# RELAY18.net
KiCad netlist of a schematic drawn in Altium Designer
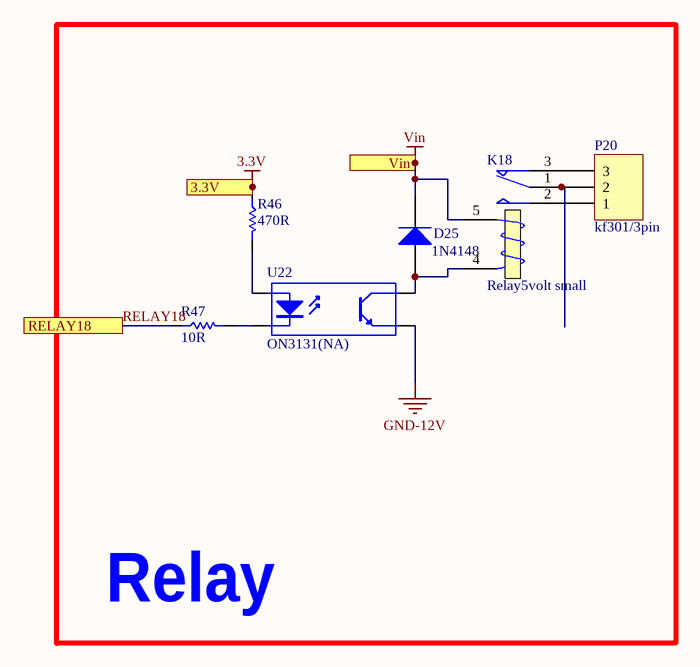
[diagram p0: RELAY18.SchDoc]

(export (version "E")
  (design (tool "Eeschema 10.0.6"))
  (components
    (comp (ref "D25")
      (value "1N4148")
      (footprint "sod123")
      (description "1 Amp General Purpose Rectifier")
      (fields (field (name "PUBLISHER") "Altium Limited"))
      (libsource (lib "Miscellaneous Devices") (part "Diode 1N4007"))
    )
    (comp (ref "K18")
      (value "Relay5volt small")
      (footprint "relay5_childern")
      (description "SPDT Relay")
      (fields (field (name "PUBLISHER") "Altium Limited"))
      (libsource (lib "FLIB") (part "Relay"))
    )
    (comp (ref "P20")
      (value "kf301/3pin")
      (footprint "Blue Connector 1*3 -kf301")
      (fields (field (name "PUBLISHER") "Altium Limited"))
      (libsource (lib "Miscellaneous Connectors") (part "Header 3"))
    )
    (comp (ref "R46")
      (value "470R")
      (footprint "0805/resistor")
      (description "Resistor")
      (fields (field (name "TOLERANCE") "5%") (field (name "POWER") "1/8 W"))
      (libsource (lib "skille") (part "Resistor"))
    )
    (comp (ref "R47")
      (value "10R")
      (footprint "0805/resistor")
      (description "Resistor")
      (fields (field (name "TOLERANCE") "5%") (field (name "POWER") "1/8 W"))
      (libsource (lib "skille") (part "Resistor"))
    )
    (comp (ref "U22")
      (value "ON3131(NA)")
      (footprint "OPTO_COUPLER")
      (description "4-Pin Phototransistor Optocoupler")
      (fields (field (name "PUBLISHER") "Altium Limited"))
      (libsource (lib "skille") (part "Optoisolator1"))
    )
  )
  (nets
    (net (code "1") (name "/RELAY18") (class "Default")
      (node (ref "R47") (pin "1") (pinfunction "1_1") (pintype "passive"))
    )
    (net (code "2") (name "3.3V") (class "Default")
      (node (ref "R46") (pin "1") (pinfunction "1_1") (pintype "passive"))
    )
    (net (code "3") (name "GND-12V") (class "Default")
      (node (ref "U22") (pin "3") (pinfunction "E_3") (pintype "passive"))
    )
    (net (code "4") (name "Net-(K18-COM)") (class "Default")
      (node (ref "K18") (pin "1") (pinfunction "COM_1") (pintype "passive"))
      (node (ref "P20") (pin "2") (pinfunction "2_2") (pintype "passive"))
    )
    (net (code "5") (name "Net-(K18-NO)") (class "Default")
      (node (ref "K18") (pin "2") (pinfunction "NO_2") (pintype "passive"))
      (node (ref "P20") (pin "1") (pinfunction "1_1") (pintype "passive"))
    )
    (net (code "6") (name "Net-(K18-T1)") (class "Default")
      (node (ref "K18") (pin "3") (pinfunction "T1_3") (pintype "passive"))
      (node (ref "P20") (pin "3") (pinfunction "3_3") (pintype "passive"))
    )
    (net (code "7") (name "Net-(K18-T2)") (class "Default")
      (node (ref "D25") (pin "A") (pinfunction "A_A") (pintype "passive"))
      (node (ref "K18") (pin "4") (pinfunction "T2_4") (pintype "passive"))
      (node (ref "U22") (pin "4") (pinfunction "C_4") (pintype "passive"))
    )
    (net (code "8") (name "Net-(U22-A)") (class "Default")
      (node (ref "R46") (pin "2") (pinfunction "2_2") (pintype "passive"))
      (node (ref "U22") (pin "1") (pinfunction "A_1") (pintype "passive"))
    )
    (net (code "9") (name "Net-(U22-K)") (class "Default")
      (node (ref "R47") (pin "2") (pinfunction "2_2") (pintype "passive"))
      (node (ref "U22") (pin "2") (pinfunction "K_2") (pintype "passive"))
    )
    (net (code "10") (name "Vin") (class "Default")
      (node (ref "D25") (pin "K") (pinfunction "K_K") (pintype "passive"))
      (node (ref "K18") (pin "5") (pinfunction "5_5") (pintype "passive"))
    )
  )
)
